# 2_USB_UART.net
KiCad netlist of a schematic drawn in Altium Designer
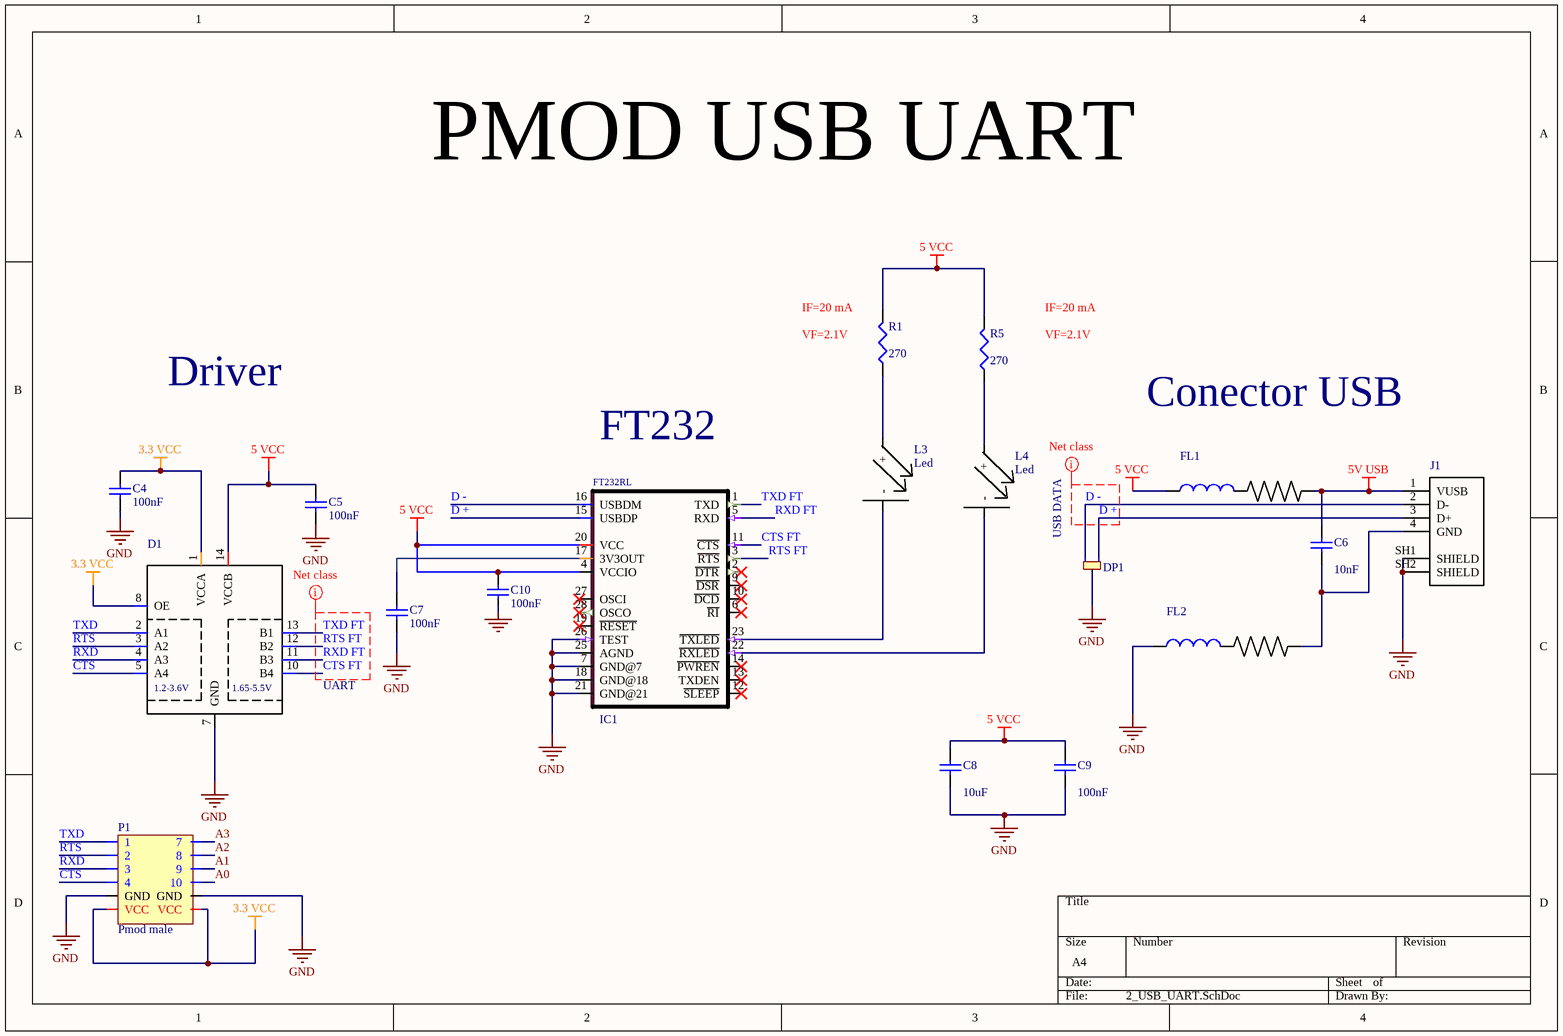
[diagram p0: 2_USB_UART.SchDoc]

(export (version "E")
  (design (tool "Eeschema 10.0.6"))
  (components
    (comp (ref "C4")
      (value "100nF")
      (footprint "1608[0603]")
      (description "Capacitor (Semiconductor SIM Model)")
      (fields (field (name "Comment") "Cap Semi") (field (name "PUBLISHER") "Altium Limited"))
      (libsource (lib "Miscellaneous Devices") (part "Cap Semi"))
    )
    (comp (ref "C5")
      (value "100nF")
      (footprint "1608[0603]")
      (description "Capacitor (Semiconductor SIM Model)")
      (fields (field (name "Comment") "Cap Semi") (field (name "PUBLISHER") "Altium Limited"))
      (libsource (lib "Miscellaneous Devices") (part "Cap Semi"))
    )
    (comp (ref "C6")
      (value "10nF")
      (footprint "1608[0603]")
      (description "Capacitor (Semiconductor SIM Model)")
      (fields (field (name "Comment") "Cap Semi") (field (name "PUBLISHER") "Altium Limited"))
      (libsource (lib "Miscellaneous Devices") (part "Cap Semi"))
    )
    (comp (ref "C7")
      (value "100nF")
      (footprint "1608[0603]")
      (description "Capacitor (Semiconductor SIM Model)")
      (fields (field (name "Comment") "Cap Semi") (field (name "PUBLISHER") "Altium Limited"))
      (libsource (lib "Miscellaneous Devices") (part "Cap Semi"))
    )
    (comp (ref "C8")
      (value "10uF")
      (footprint "1608[0603]")
      (description "Capacitor (Semiconductor SIM Model)")
      (fields (field (name "Comment") "Cap Semi") (field (name "PUBLISHER") "Altium Limited"))
      (libsource (lib "Miscellaneous Devices") (part "Cap Semi"))
    )
    (comp (ref "C9")
      (value "100nF")
      (footprint "1608[0603]")
      (description "Capacitor (Semiconductor SIM Model)")
      (fields (field (name "Comment") "Cap Semi") (field (name "PUBLISHER") "Altium Limited"))
      (libsource (lib "Miscellaneous Devices") (part "Cap Semi"))
    )
    (comp (ref "C10")
      (value "100nF")
      (footprint "1608[0603]")
      (description "Capacitor (Semiconductor SIM Model)")
      (fields (field (name "Comment") "Cap Semi") (field (name "PUBLISHER") "Altium Limited"))
      (libsource (lib "Miscellaneous Devices") (part "Cap Semi"))
    )
    (comp (ref "D1")
      (value "TXB0104PWR")
      (footprint "*TSSOP14")
      (fields (field (name "MF") "Texas Instruments"))
      (libsource (lib "Schlib1") (part "TXB0104PWR"))
    )
    (comp (ref "DP1")
      (value "PESD5V0U2BT,215")
      (footprint "*SOT95P230X110-3N")
      (description "TVS DIODE 5V SOT23")
      (libsource (lib "Schlib1") (part "PESD5V0U2BT,215"))
    )
    (comp (ref "FL1")
      (value "BLM21PG221SN1D")
      (footprint "*BEADC2012X105N")
      (description "220 Ohms @ 100MHz 1 Power Line Ferrite Bead 0805 (2012 Metric) 2A 45mOhm")
      (fields (field (name "MF") "Murata") (field (name "DIGI-KEY_PART_NUMBER") "490-1054-1-ND"))
      (libsource (lib "Schlib1") (part "BLM21PG221SN1D"))
    )
    (comp (ref "FL2")
      (value "BLM21PG221SN1D")
      (footprint "*BEADC2012X105N")
      (description "220 Ohms @ 100MHz 1 Power Line Ferrite Bead 0805 (2012 Metric) 2A 45mOhm")
      (fields (field (name "MF") "Murata") (field (name "DIGI-KEY_PART_NUMBER") "490-1054-1-ND"))
      (libsource (lib "Schlib1") (part "BLM21PG221SN1D"))
    )
    (comp (ref "IC1")
      (value "FT232RL")
      (footprint "*SSOP28-LD")
      (description "USB-to-UART 1-CH 256Byte FIFO 5V 28-Pin SSOP")
      (fields (field (name "MF") "FTDI, Future"))
      (libsource (lib "Schlib1") (part "FT232RL"))
    )
    (comp (ref "J1")
      (value "1-1734346-1")
      (footprint "*TE_1-1734346-1_1-1734346-1(Primary)")
      (description "Conn USB 2.0 Type B RCP 4 POS 1.25mm Solder RA SMD 4 Terminal 1 Port T/R")
      (fields (field (name "MF") "TE Connectivity") (field (name "DIGI-KEY_PART_NUMBER") "A110862CT-ND"))
      (libsource (lib "Schlib1") (part "1-1734346-1"))
    )
    (comp (ref "L3")
      (value "Led")
      (footprint "Diode1206 - PIN LETTER")
      (libsource (lib "Schlib1") (part "Led"))
    )
    (comp (ref "L4")
      (value "Led")
      (footprint "Diode1206 - PIN LETTER")
      (libsource (lib "Schlib1") (part "Led"))
    )
    (comp (ref "P1")
      (value "Pmod male")
      (footprint "901220766")
      (description "p mod male 6 position 2 rows")
      (libsource (lib "Schlib1") (part "Pmod male"))
    )
    (comp (ref "R1")
      (value "270")
      (footprint "J1-0603")
      (description "Resistor")
      (fields (field (name "Comment") "270R") (field (name "PUBLISHER") "Altium Limited"))
      (libsource (lib "Miscellaneous Devices") (part "Res3"))
    )
    (comp (ref "R5")
      (value "270")
      (footprint "J1-0603")
      (description "Resistor")
      (fields (field (name "Comment") "270R") (field (name "PUBLISHER") "Altium Limited"))
      (libsource (lib "Miscellaneous Devices") (part "Res3"))
    )
  )
  (nets
    (net (code "1") (name "/A0") (class "Default")
      (node (ref "P1") (pin "10") (pinfunction "10_10") (pintype "passive"))
    )
    (net (code "2") (name "/A1") (class "Default")
      (node (ref "P1") (pin "9") (pinfunction "9_9") (pintype "passive"))
    )
    (net (code "3") (name "/A2") (class "Default")
      (node (ref "P1") (pin "8") (pinfunction "8_8") (pintype "passive"))
    )
    (net (code "4") (name "/A3") (class "Default")
      (node (ref "P1") (pin "7") (pinfunction "7_7") (pintype "passive"))
    )
    (net (code "5") (name "/CTS") (class "Default")
      (node (ref "D1") (pin "5") (pinfunction "A4_5") (pintype "bidirectional"))
      (node (ref "P1") (pin "4") (pinfunction "4_4") (pintype "passive"))
    )
    (net (code "6") (name "/CTS FT") (class "Default")
      (node (ref "D1") (pin "10") (pinfunction "B4_10") (pintype "bidirectional"))
      (node (ref "IC1") (pin "11") (pinfunction "~{CTS}_11") (pintype "input"))
    )
    (net (code "7") (name "/D +") (class "Default")
      (node (ref "DP1") (pin "1") (pinfunction "1_1") (pintype "passive"))
      (node (ref "IC1") (pin "15") (pinfunction "USBDP_15") (pintype "bidirectional"))
      (node (ref "J1") (pin "3") (pinfunction "D+_3") (pintype "passive"))
    )
    (net (code "8") (name "/D -") (class "Default")
      (node (ref "DP1") (pin "2") (pinfunction "2_2") (pintype "passive"))
      (node (ref "IC1") (pin "16") (pinfunction "USBDM_16") (pintype "bidirectional"))
      (node (ref "J1") (pin "2") (pinfunction "D-_2") (pintype "passive"))
    )
    (net (code "9") (name "/RTS") (class "Default")
      (node (ref "D1") (pin "3") (pinfunction "A2_3") (pintype "bidirectional"))
      (node (ref "P1") (pin "2") (pinfunction "2_2") (pintype "passive"))
    )
    (net (code "10") (name "/RTS FT") (class "Default")
      (node (ref "D1") (pin "12") (pinfunction "B2_12") (pintype "bidirectional"))
      (node (ref "IC1") (pin "3") (pinfunction "~{RTS}_3") (pintype "output"))
    )
    (net (code "11") (name "/RXD") (class "Default")
      (node (ref "D1") (pin "4") (pinfunction "A3_4") (pintype "bidirectional"))
      (node (ref "P1") (pin "3") (pinfunction "3_3") (pintype "passive"))
    )
    (net (code "12") (name "/RXD FT") (class "Default")
      (node (ref "D1") (pin "11") (pinfunction "B3_11") (pintype "bidirectional"))
      (node (ref "IC1") (pin "5") (pinfunction "RXD_5") (pintype "input"))
    )
    (net (code "13") (name "/TXD") (class "Default")
      (node (ref "D1") (pin "2") (pinfunction "A1_2") (pintype "bidirectional"))
      (node (ref "P1") (pin "1") (pinfunction "1_1") (pintype "passive"))
    )
    (net (code "14") (name "/TXD FT") (class "Default")
      (node (ref "D1") (pin "13") (pinfunction "B1_13") (pintype "bidirectional"))
      (node (ref "IC1") (pin "1") (pinfunction "TXD_1") (pintype "output"))
    )
    (net (code "15") (name "3.3 VCC") (class "Default")
      (node (ref "C4") (pin "1") (pinfunction "1_1") (pintype "passive"))
      (node (ref "D1") (pin "1") (pinfunction "VCCA_1") (pintype "bidirectional"))
      (node (ref "D1") (pin "8") (pinfunction "OE_8") (pintype "bidirectional"))
      (node (ref "P1") (pin "12") (pinfunction "VCC_12") (pintype "passive"))
      (node (ref "P1") (pin "6") (pinfunction "VCC_6") (pintype "passive"))
    )
    (net (code "16") (name "5 VCC") (class "Default")
      (node (ref "C10") (pin "1") (pinfunction "1_1") (pintype "passive"))
      (node (ref "C5") (pin "1") (pinfunction "1_1") (pintype "passive"))
      (node (ref "C8") (pin "2") (pinfunction "2_2") (pintype "passive"))
      (node (ref "C9") (pin "2") (pinfunction "2_2") (pintype "passive"))
      (node (ref "D1") (pin "14") (pinfunction "VCCB_14") (pintype "bidirectional"))
      (node (ref "FL1") (pin "1") (pinfunction "1_1") (pintype "passive"))
      (node (ref "IC1") (pin "20") (pinfunction "VCC_20") (pintype "power_in"))
      (node (ref "IC1") (pin "4") (pinfunction "VCCIO_4") (pintype "power_in"))
      (node (ref "R1") (pin "2") (pinfunction "2_2") (pintype "passive"))
      (node (ref "R5") (pin "2") (pinfunction "2_2") (pintype "passive"))
    )
    (net (code "17") (name "5V USB") (class "Default")
      (node (ref "C6") (pin "2") (pinfunction "2_2") (pintype "passive"))
      (node (ref "FL1") (pin "2") (pinfunction "2_2") (pintype "passive"))
      (node (ref "J1") (pin "1") (pinfunction "VUSB_1") (pintype "passive"))
    )
    (net (code "18") (name "GND") (class "Default")
      (node (ref "C10") (pin "2") (pinfunction "2_2") (pintype "passive"))
      (node (ref "C4") (pin "2") (pinfunction "2_2") (pintype "passive"))
      (node (ref "C5") (pin "2") (pinfunction "2_2") (pintype "passive"))
      (node (ref "C7") (pin "2") (pinfunction "2_2") (pintype "passive"))
      (node (ref "C8") (pin "1") (pinfunction "1_1") (pintype "passive"))
      (node (ref "C9") (pin "1") (pinfunction "1_1") (pintype "passive"))
      (node (ref "D1") (pin "7") (pinfunction "GND_7") (pintype "bidirectional"))
      (node (ref "DP1") (pin "3") (pinfunction "3_3") (pintype "passive"))
      (node (ref "FL2") (pin "1") (pinfunction "1_1") (pintype "passive"))
      (node (ref "IC1") (pin "18") (pinfunction "GND@18_18") (pintype "power_in"))
      (node (ref "IC1") (pin "21") (pinfunction "GND@21_21") (pintype "power_in"))
      (node (ref "IC1") (pin "25") (pinfunction "AGND_25") (pintype "power_in"))
      (node (ref "IC1") (pin "26") (pinfunction "TEST_26") (pintype "input"))
      (node (ref "IC1") (pin "7") (pinfunction "GND@7_7") (pintype "power_in"))
      (node (ref "J1") (pin "SH1") (pinfunction "SHIELD_SH1") (pintype "passive"))
      (node (ref "J1") (pin "SH2") (pinfunction "SHIELD_SH2") (pintype "passive"))
      (node (ref "P1") (pin "11") (pinfunction "GND_11") (pintype "passive"))
      (node (ref "P1") (pin "5") (pinfunction "GND_5") (pintype "passive"))
    )
    (net (code "19") (name "Net-(IC1-3V3OUT)") (class "Default")
      (node (ref "C7") (pin "1") (pinfunction "1_1") (pintype "passive"))
      (node (ref "IC1") (pin "17") (pinfunction "3V3OUT_17") (pintype "power_in"))
    )
    (net (code "20") (name "Net-(IC1-~{RXLED})") (class "Default")
      (node (ref "IC1") (pin "22") (pinfunction "~{RXLED}_22") (pintype "input"))
      (node (ref "L4") (pin "K") (pinfunction "-_K") (pintype "passive"))
    )
    (net (code "21") (name "Net-(IC1-~{TXLED})") (class "Default")
      (node (ref "IC1") (pin "23") (pinfunction "~{TXLED}_23") (pintype "input"))
      (node (ref "L3") (pin "K") (pinfunction "-_K") (pintype "passive"))
    )
    (net (code "22") (name "Net-(J1-GND)") (class "Default")
      (node (ref "C6") (pin "1") (pinfunction "1_1") (pintype "passive"))
      (node (ref "FL2") (pin "2") (pinfunction "2_2") (pintype "passive"))
      (node (ref "J1") (pin "4") (pinfunction "GND_4") (pintype "passive"))
    )
    (net (code "23") (name "Net-(L3-+)") (class "Default")
      (node (ref "L3") (pin "A") (pinfunction "+_A") (pintype "passive"))
      (node (ref "R1") (pin "1") (pinfunction "1_1") (pintype "passive"))
    )
    (net (code "24") (name "Net-(L4-+)") (class "Default")
      (node (ref "L4") (pin "A") (pinfunction "+_A") (pintype "passive"))
      (node (ref "R5") (pin "1") (pinfunction "1_1") (pintype "passive"))
    )
    (net (code "25") (name "unconnected-(IC1-OSCI-Pad27)") (class "Default")
      (node (ref "IC1") (pin "27") (pinfunction "OSCI_27") (pintype "passive+no_connect"))
    )
    (net (code "26") (name "unconnected-(IC1-OSCO-Pad28)") (class "Default")
      (node (ref "IC1") (pin "28") (pinfunction "OSCO_28") (pintype "output+no_connect"))
    )
    (net (code "27") (name "unconnected-(IC1-TXDEN-Pad13)") (class "Default")
      (node (ref "IC1") (pin "13") (pinfunction "TXDEN_13") (pintype "passive+no_connect"))
    )
    (net (code "28") (name "unconnected-(IC1-~{DCD}-Pad10)") (class "Default")
      (node (ref "IC1") (pin "10") (pinfunction "~{DCD}_10") (pintype "passive+no_connect"))
    )
    (net (code "29") (name "unconnected-(IC1-~{DSR}-Pad9)") (class "Default")
      (node (ref "IC1") (pin "9") (pinfunction "~{DSR}_9") (pintype "passive+no_connect"))
    )
    (net (code "30") (name "unconnected-(IC1-~{DTR}-Pad2)") (class "Default")
      (node (ref "IC1") (pin "2") (pinfunction "~{DTR}_2") (pintype "output+no_connect"))
    )
    (net (code "31") (name "unconnected-(IC1-~{PWREN}-Pad14)") (class "Default")
      (node (ref "IC1") (pin "14") (pinfunction "~{PWREN}_14") (pintype "passive+no_connect"))
    )
    (net (code "32") (name "unconnected-(IC1-~{RESET}-Pad19)") (class "Default")
      (node (ref "IC1") (pin "19") (pinfunction "~{RESET}_19") (pintype "passive+no_connect"))
    )
    (net (code "33") (name "unconnected-(IC1-~{RI}-Pad6)") (class "Default")
      (node (ref "IC1") (pin "6") (pinfunction "~{RI}_6") (pintype "passive+no_connect"))
    )
    (net (code "34") (name "unconnected-(IC1-~{SLEEP}-Pad12)") (class "Default")
      (node (ref "IC1") (pin "12") (pinfunction "~{SLEEP}_12") (pintype "passive+no_connect"))
    )
  )
)
